# Attenuator.net
KiCad netlist of a schematic drawn in EAGLE
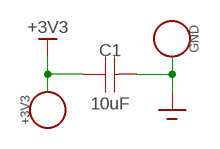
[diagram p0: schematic, sheet 1]
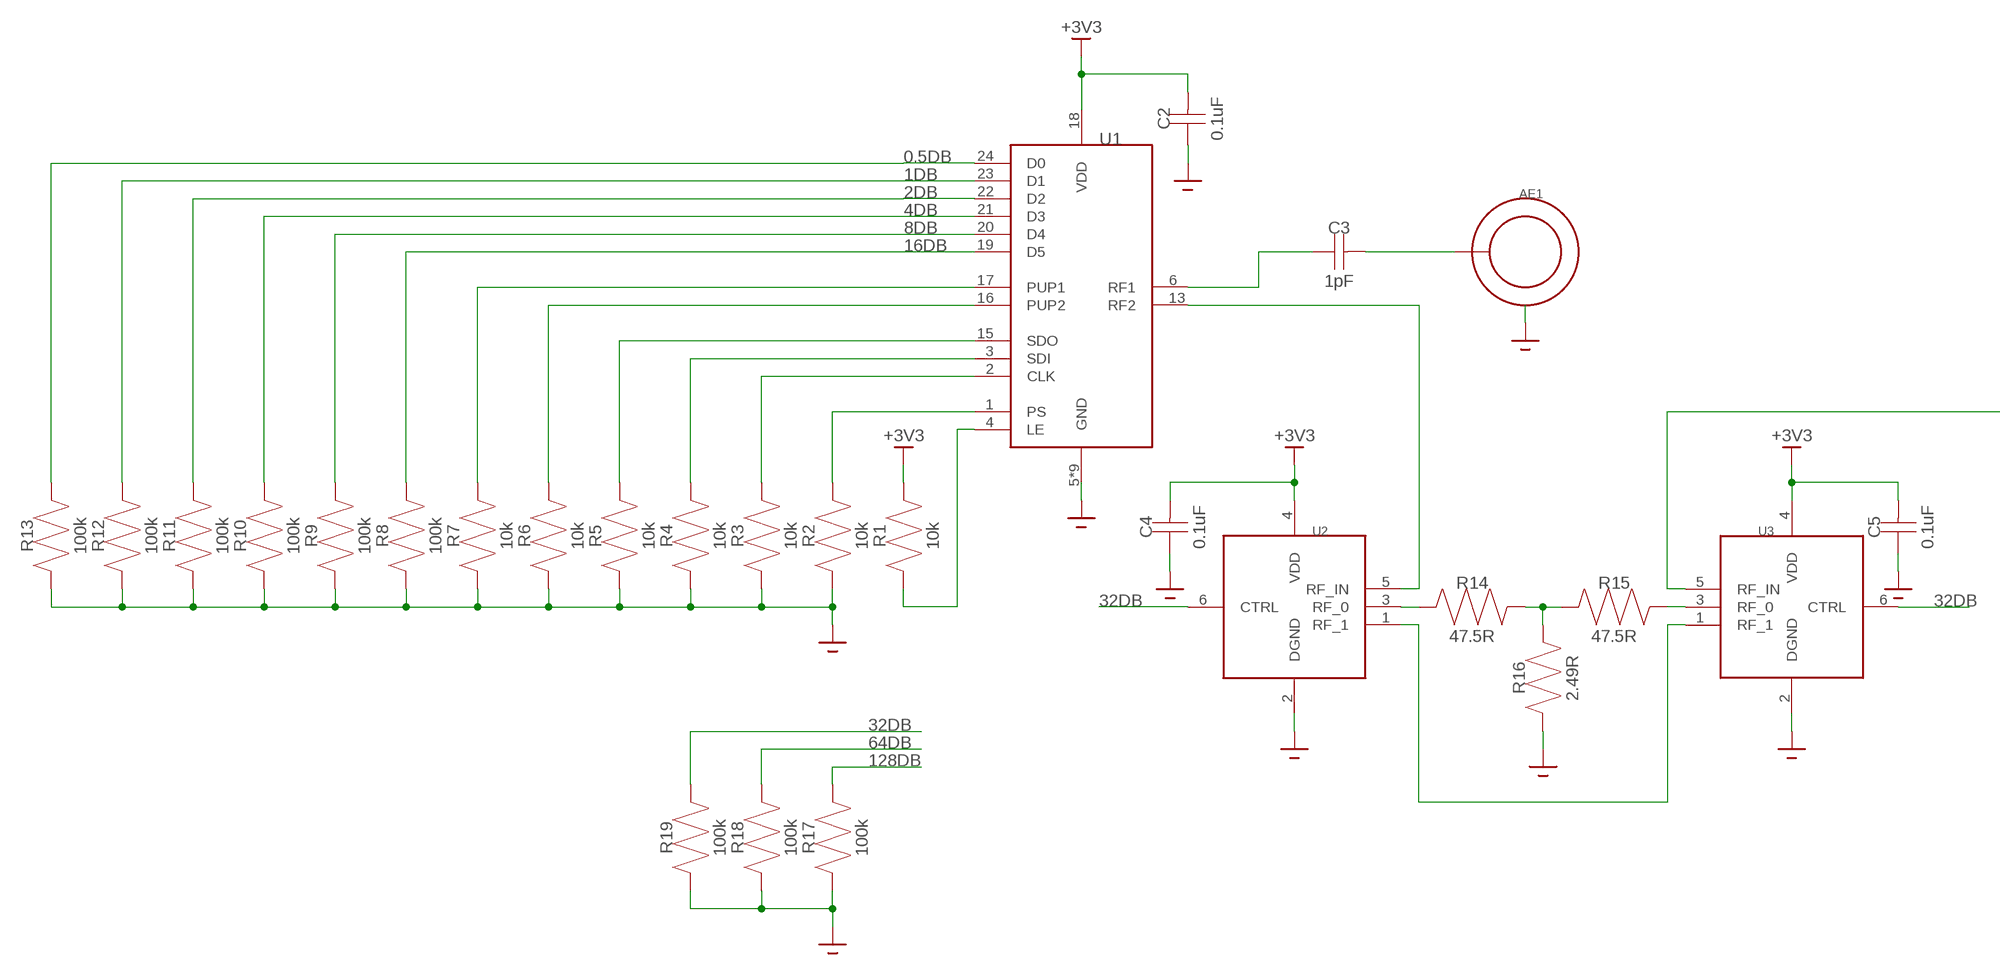
[diagram p1: schematic, sheet 2, part 1 of 2]
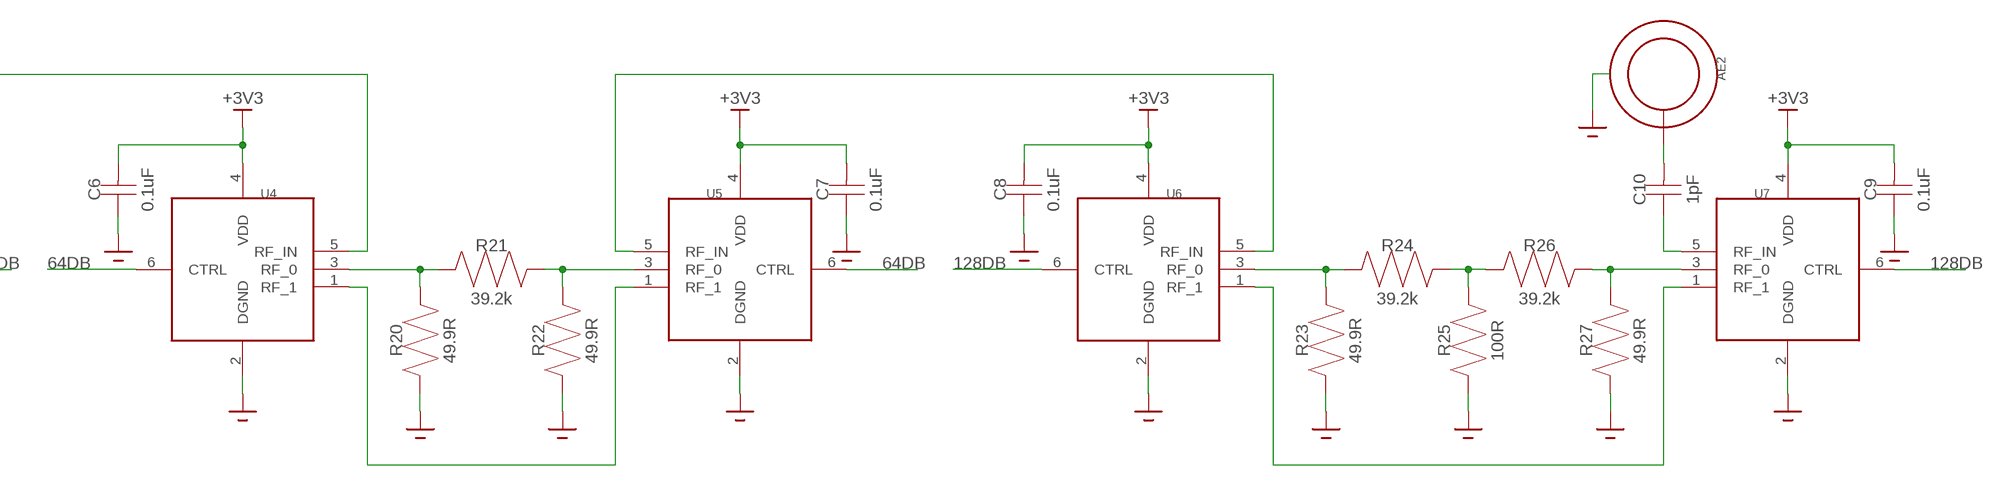
[diagram p2: schematic, sheet 2, part 2 of 2]
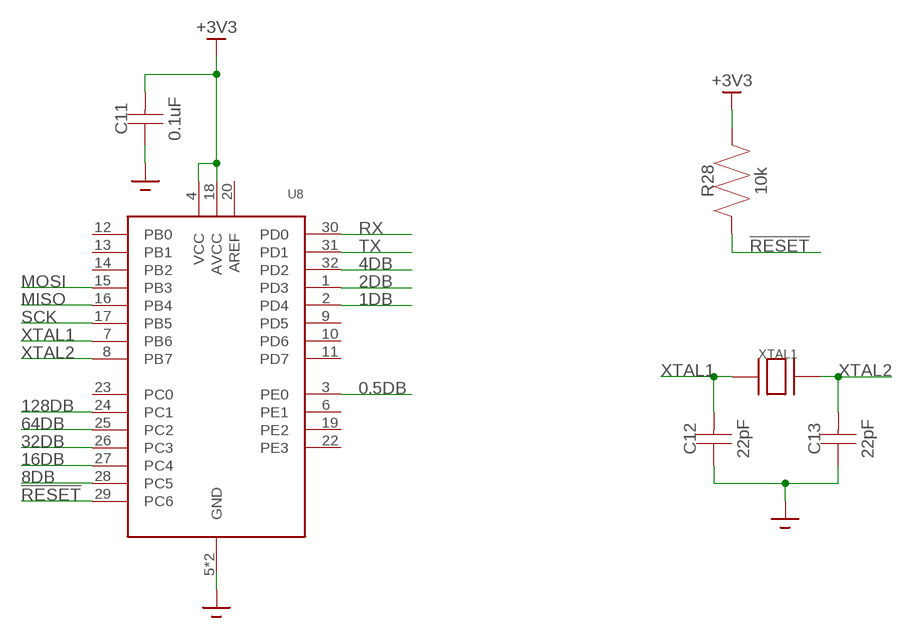
[diagram p3: schematic, sheet 3]
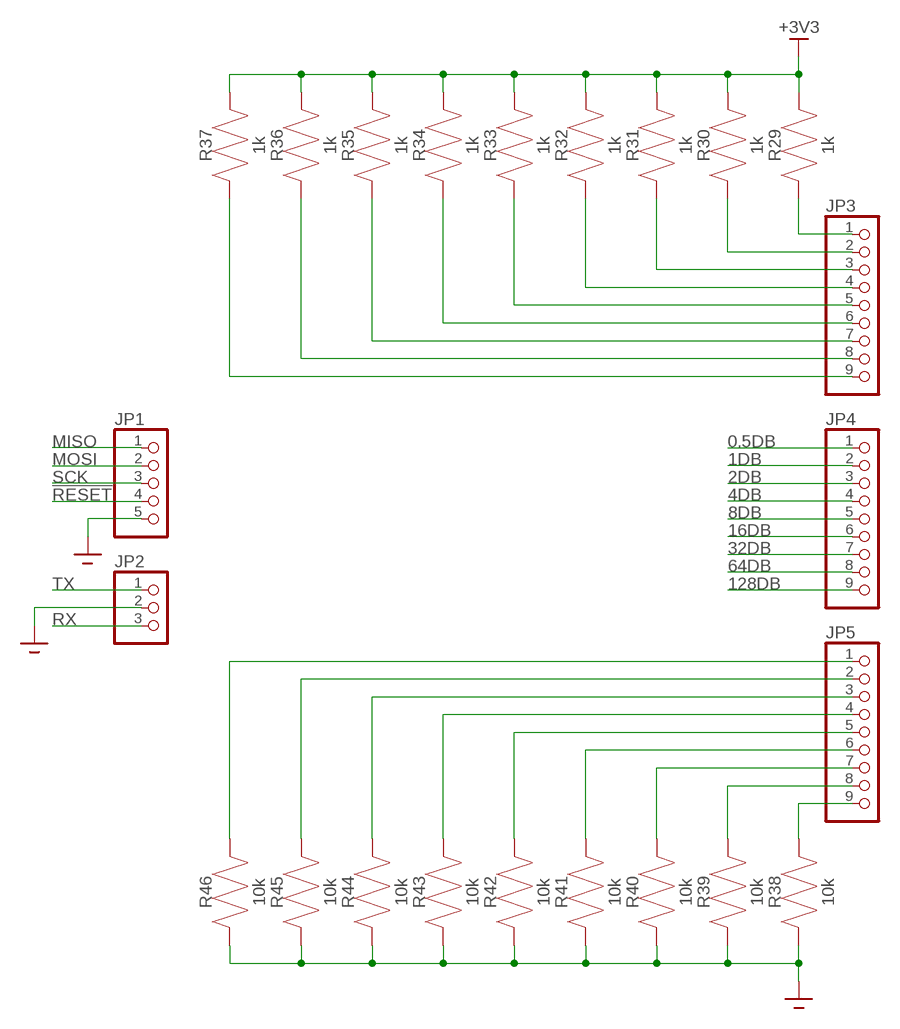
[diagram p4: schematic, sheet 4]

(export (version "E")
  (design (tool "Eeschema 10.0.6"))
  (components
    (comp (ref "C11")
      (value "0.1uF")
      (footprint "eagle-import:0805")
      (libsource (lib "eagle-import") (part "CAPACITOR0805"))
    )
    (comp (ref "C12")
      (value "22pF")
      (footprint "eagle-import:0805")
      (libsource (lib "eagle-import") (part "CAPACITOR0805"))
    )
    (comp (ref "C13")
      (value "22pF")
      (footprint "eagle-import:0805")
      (libsource (lib "eagle-import") (part "CAPACITOR0805"))
    )
    (comp (ref "R28")
      (value "10k")
      (footprint "eagle-import:0805")
      (libsource (lib "eagle-import") (part "RESISTOR0805"))
    )
    (comp (ref "U8")
      (value "ATMEGA328PB32-TQFP")
      (footprint "eagle-import:QFP80P900X900X120-32")
      (libsource (lib "eagle-import") (part "ATMEGA328PB32-TQFP"))
    )
    (comp (ref "XTAL1")
      (value "CRYSTAL")
      (footprint "eagle-import:ABM2")
      (libsource (lib "eagle-import") (part "CRYSTAL"))
    )
    (comp (ref "JP1")
      (value "PINHD-1X5")
      (footprint "eagle-import:1X05")
      (libsource (lib "eagle-import") (part "PINHD-1X5"))
    )
    (comp (ref "JP2")
      (value "PINHD-1X3")
      (footprint "eagle-import:1X03")
      (libsource (lib "eagle-import") (part "PINHD-1X3"))
    )
    (comp (ref "JP3")
      (value "PINHD-1X9")
      (footprint "eagle-import:1X09")
      (libsource (lib "eagle-import") (part "PINHD-1X9"))
    )
    (comp (ref "JP4")
      (value "PINHD-1X9")
      (footprint "eagle-import:1X09")
      (libsource (lib "eagle-import") (part "PINHD-1X9"))
    )
    (comp (ref "JP5")
      (value "PINHD-1X9")
      (footprint "eagle-import:1X09")
      (libsource (lib "eagle-import") (part "PINHD-1X9"))
    )
    (comp (ref "R29")
      (value "1k")
      (footprint "eagle-import:0805")
      (libsource (lib "eagle-import") (part "RESISTOR0805"))
    )
    (comp (ref "R30")
      (value "1k")
      (footprint "eagle-import:0805")
      (libsource (lib "eagle-import") (part "RESISTOR0805"))
    )
    (comp (ref "R31")
      (value "1k")
      (footprint "eagle-import:0805")
      (libsource (lib "eagle-import") (part "RESISTOR0805"))
    )
    (comp (ref "R32")
      (value "1k")
      (footprint "eagle-import:0805")
      (libsource (lib "eagle-import") (part "RESISTOR0805"))
    )
    (comp (ref "R33")
      (value "1k")
      (footprint "eagle-import:0805")
      (libsource (lib "eagle-import") (part "RESISTOR0805"))
    )
    (comp (ref "R34")
      (value "1k")
      (footprint "eagle-import:0805")
      (libsource (lib "eagle-import") (part "RESISTOR0805"))
    )
    (comp (ref "R35")
      (value "1k")
      (footprint "eagle-import:0805")
      (libsource (lib "eagle-import") (part "RESISTOR0805"))
    )
    (comp (ref "R36")
      (value "1k")
      (footprint "eagle-import:0805")
      (libsource (lib "eagle-import") (part "RESISTOR0805"))
    )
    (comp (ref "R37")
      (value "1k")
      (footprint "eagle-import:0805")
      (libsource (lib "eagle-import") (part "RESISTOR0805"))
    )
    (comp (ref "R38")
      (value "10k")
      (footprint "eagle-import:0805")
      (libsource (lib "eagle-import") (part "RESISTOR0805"))
    )
    (comp (ref "R39")
      (value "10k")
      (footprint "eagle-import:0805")
      (libsource (lib "eagle-import") (part "RESISTOR0805"))
    )
    (comp (ref "R40")
      (value "10k")
      (footprint "eagle-import:0805")
      (libsource (lib "eagle-import") (part "RESISTOR0805"))
    )
    (comp (ref "R41")
      (value "10k")
      (footprint "eagle-import:0805")
      (libsource (lib "eagle-import") (part "RESISTOR0805"))
    )
    (comp (ref "R42")
      (value "10k")
      (footprint "eagle-import:0805")
      (libsource (lib "eagle-import") (part "RESISTOR0805"))
    )
    (comp (ref "R43")
      (value "10k")
      (footprint "eagle-import:0805")
      (libsource (lib "eagle-import") (part "RESISTOR0805"))
    )
    (comp (ref "R44")
      (value "10k")
      (footprint "eagle-import:0805")
      (libsource (lib "eagle-import") (part "RESISTOR0805"))
    )
    (comp (ref "R45")
      (value "10k")
      (footprint "eagle-import:0805")
      (libsource (lib "eagle-import") (part "RESISTOR0805"))
    )
    (comp (ref "R46")
      (value "10k")
      (footprint "eagle-import:0805")
      (libsource (lib "eagle-import") (part "RESISTOR0805"))
    )
    (comp (ref "C1")
      (value "10uF")
      (footprint "eagle-import:0805")
      (libsource (lib "eagle-import") (part "CAPACITOR0805"))
    )
    (comp (ref "TP1")
      (value "+3V3")
      (footprint "eagle-import:ALIGATOR-PAD")
      (libsource (lib "eagle-import") (part "ALIGATOR-PAD"))
    )
    (comp (ref "TP2")
      (value "GND")
      (footprint "eagle-import:ALIGATOR-PAD")
      (libsource (lib "eagle-import") (part "ALIGATOR-PAD"))
    )
    (comp (ref "AE1")
      (value "CON-SMA-EDGE-S")
      (footprint "eagle-import:CON-SMA-EDGE-S")
      (libsource (lib "eagle-import") (part "CON-SMA-EDGE-S"))
    )
    (comp (ref "AE2")
      (value "CON-SMA-EDGE-S")
      (footprint "eagle-import:CON-SMA-EDGE-S")
      (libsource (lib "eagle-import") (part "CON-SMA-EDGE-S"))
    )
    (comp (ref "C2")
      (value "0.1uF")
      (footprint "eagle-import:0805")
      (libsource (lib "eagle-import") (part "CAPACITOR0805"))
    )
    (comp (ref "C3")
      (value "1pF")
      (footprint "eagle-import:0805")
      (libsource (lib "eagle-import") (part "CAPACITOR0805"))
    )
    (comp (ref "C4")
      (value "0.1uF")
      (footprint "eagle-import:0805")
      (libsource (lib "eagle-import") (part "CAPACITOR0805"))
    )
    (comp (ref "C5")
      (value "0.1uF")
      (footprint "eagle-import:0805")
      (libsource (lib "eagle-import") (part "CAPACITOR0805"))
    )
    (comp (ref "C6")
      (value "0.1uF")
      (footprint "eagle-import:0805")
      (libsource (lib "eagle-import") (part "CAPACITOR0805"))
    )
    (comp (ref "C7")
      (value "0.1uF")
      (footprint "eagle-import:0805")
      (libsource (lib "eagle-import") (part "CAPACITOR0805"))
    )
    (comp (ref "C8")
      (value "0.1uF")
      (footprint "eagle-import:0805")
      (libsource (lib "eagle-import") (part "CAPACITOR0805"))
    )
    (comp (ref "C9")
      (value "0.1uF")
      (footprint "eagle-import:0805")
      (libsource (lib "eagle-import") (part "CAPACITOR0805"))
    )
    (comp (ref "C10")
      (value "1pF")
      (footprint "eagle-import:0805")
      (libsource (lib "eagle-import") (part "CAPACITOR0805"))
    )
    (comp (ref "R1")
      (value "10k")
      (footprint "eagle-import:0805")
      (libsource (lib "eagle-import") (part "RESISTOR0805"))
    )
    (comp (ref "R2")
      (value "10k")
      (footprint "eagle-import:0805")
      (libsource (lib "eagle-import") (part "RESISTOR0805"))
    )
    (comp (ref "R3")
      (value "10k")
      (footprint "eagle-import:0805")
      (libsource (lib "eagle-import") (part "RESISTOR0805"))
    )
    (comp (ref "R4")
      (value "10k")
      (footprint "eagle-import:0805")
      (libsource (lib "eagle-import") (part "RESISTOR0805"))
    )
    (comp (ref "R5")
      (value "10k")
      (footprint "eagle-import:0805")
      (libsource (lib "eagle-import") (part "RESISTOR0805"))
    )
    (comp (ref "R6")
      (value "10k")
      (footprint "eagle-import:0805")
      (libsource (lib "eagle-import") (part "RESISTOR0805"))
    )
    (comp (ref "R7")
      (value "10k")
      (footprint "eagle-import:0805")
      (libsource (lib "eagle-import") (part "RESISTOR0805"))
    )
    (comp (ref "R8")
      (value "100k")
      (footprint "eagle-import:0805")
      (libsource (lib "eagle-import") (part "RESISTOR0805"))
    )
    (comp (ref "R9")
      (value "100k")
      (footprint "eagle-import:0805")
      (libsource (lib "eagle-import") (part "RESISTOR0805"))
    )
    (comp (ref "R10")
      (value "100k")
      (footprint "eagle-import:0805")
      (libsource (lib "eagle-import") (part "RESISTOR0805"))
    )
    (comp (ref "R11")
      (value "100k")
      (footprint "eagle-import:0805")
      (libsource (lib "eagle-import") (part "RESISTOR0805"))
    )
    (comp (ref "R12")
      (value "100k")
      (footprint "eagle-import:0805")
      (libsource (lib "eagle-import") (part "RESISTOR0805"))
    )
    (comp (ref "R13")
      (value "100k")
      (footprint "eagle-import:0805")
      (libsource (lib "eagle-import") (part "RESISTOR0805"))
    )
    (comp (ref "R14")
      (value "47.5R")
      (footprint "eagle-import:0805")
      (libsource (lib "eagle-import") (part "RESISTOR0805"))
    )
    (comp (ref "R15")
      (value "47.5R")
      (footprint "eagle-import:0805")
      (libsource (lib "eagle-import") (part "RESISTOR0805"))
    )
    (comp (ref "R16")
      (value "2.49R")
      (footprint "eagle-import:0805")
      (libsource (lib "eagle-import") (part "RESISTOR0805"))
    )
    (comp (ref "R17")
      (value "100k")
      (footprint "eagle-import:0805")
      (libsource (lib "eagle-import") (part "RESISTOR0805"))
    )
    (comp (ref "R18")
      (value "100k")
      (footprint "eagle-import:0805")
      (libsource (lib "eagle-import") (part "RESISTOR0805"))
    )
    (comp (ref "R19")
      (value "100k")
      (footprint "eagle-import:0805")
      (libsource (lib "eagle-import") (part "RESISTOR0805"))
    )
    (comp (ref "R20")
      (value "49.9R")
      (footprint "eagle-import:0805")
      (libsource (lib "eagle-import") (part "RESISTOR0805"))
    )
    (comp (ref "R21")
      (value "39.2k")
      (footprint "eagle-import:0805")
      (libsource (lib "eagle-import") (part "RESISTOR0805"))
    )
    (comp (ref "R22")
      (value "49.9R")
      (footprint "eagle-import:0805")
      (libsource (lib "eagle-import") (part "RESISTOR0805"))
    )
    (comp (ref "R23")
      (value "49.9R")
      (footprint "eagle-import:0805")
      (libsource (lib "eagle-import") (part "RESISTOR0805"))
    )
    (comp (ref "R24")
      (value "39.2k")
      (footprint "eagle-import:0805")
      (libsource (lib "eagle-import") (part "RESISTOR0805"))
    )
    (comp (ref "R25")
      (value "100R")
      (footprint "eagle-import:0805")
      (libsource (lib "eagle-import") (part "RESISTOR0805"))
    )
    (comp (ref "R26")
      (value "39.2k")
      (footprint "eagle-import:0805")
      (libsource (lib "eagle-import") (part "RESISTOR0805"))
    )
    (comp (ref "R27")
      (value "49.9R")
      (footprint "eagle-import:0805")
      (libsource (lib "eagle-import") (part "RESISTOR0805"))
    )
    (comp (ref "U1")
      (value "SKY12347-362LF")
      (footprint "eagle-import:QFN50P400X400X100-25T270N")
      (libsource (lib "eagle-import") (part "SKY12347-362LF"))
    )
    (comp (ref "U2")
      (value "BGS12SN6E6327XTSA1")
      (footprint "eagle-import:SON40P70X110X40-6N")
      (libsource (lib "eagle-import") (part "BGS12SN6E6327XTSA1"))
    )
    (comp (ref "U3")
      (value "BGS12SN6E6327XTSA1")
      (footprint "eagle-import:SON40P70X110X40-6N")
      (libsource (lib "eagle-import") (part "BGS12SN6E6327XTSA1"))
    )
    (comp (ref "U4")
      (value "BGS12SN6E6327XTSA1")
      (footprint "eagle-import:SON40P70X110X40-6N")
      (libsource (lib "eagle-import") (part "BGS12SN6E6327XTSA1"))
    )
    (comp (ref "U5")
      (value "BGS12SN6E6327XTSA1")
      (footprint "eagle-import:SON40P70X110X40-6N")
      (libsource (lib "eagle-import") (part "BGS12SN6E6327XTSA1"))
    )
    (comp (ref "U6")
      (value "BGS12SN6E6327XTSA1")
      (footprint "eagle-import:SON40P70X110X40-6N")
      (libsource (lib "eagle-import") (part "BGS12SN6E6327XTSA1"))
    )
    (comp (ref "U7")
      (value "BGS12SN6E6327XTSA1")
      (footprint "eagle-import:SON40P70X110X40-6N")
      (libsource (lib "eagle-import") (part "BGS12SN6E6327XTSA1"))
    )
  )
  (nets
    (net (code "1") (name "+3V3") (class "Default")
      (node (ref "C1") (pin "P$1") (pinfunction "P$1_P$1") (pintype "passive"))
      (node (ref "C11") (pin "P$2") (pinfunction "P$2_P$2") (pintype "passive"))
      (node (ref "C2") (pin "P$2") (pinfunction "P$2_P$2") (pintype "passive"))
      (node (ref "C4") (pin "P$2") (pinfunction "P$2_P$2") (pintype "passive"))
      (node (ref "C5") (pin "P$2") (pinfunction "P$2_P$2") (pintype "passive"))
      (node (ref "C6") (pin "P$2") (pinfunction "P$2_P$2") (pintype "passive"))
      (node (ref "C7") (pin "P$2") (pinfunction "P$2_P$2") (pintype "passive"))
      (node (ref "C8") (pin "P$2") (pinfunction "P$2_P$2") (pintype "passive"))
      (node (ref "C9") (pin "P$2") (pinfunction "P$2_P$2") (pintype "passive"))
      (node (ref "R1") (pin "P$2") (pinfunction "P$2_P$2") (pintype "passive"))
      (node (ref "R28") (pin "P$2") (pinfunction "P$2_P$2") (pintype "passive"))
      (node (ref "R29") (pin "P$2") (pinfunction "P$2_P$2") (pintype "passive"))
      (node (ref "R30") (pin "P$2") (pinfunction "P$2_P$2") (pintype "passive"))
      (node (ref "R31") (pin "P$2") (pinfunction "P$2_P$2") (pintype "passive"))
      (node (ref "R32") (pin "P$2") (pinfunction "P$2_P$2") (pintype "passive"))
      (node (ref "R33") (pin "P$2") (pinfunction "P$2_P$2") (pintype "passive"))
      (node (ref "R34") (pin "P$2") (pinfunction "P$2_P$2") (pintype "passive"))
      (node (ref "R35") (pin "P$2") (pinfunction "P$2_P$2") (pintype "passive"))
      (node (ref "R36") (pin "P$2") (pinfunction "P$2_P$2") (pintype "passive"))
      (node (ref "R37") (pin "P$2") (pinfunction "P$2_P$2") (pintype "passive"))
      (node (ref "TP1") (pin "P$1") (pinfunction "P$1_P$1") (pintype "bidirectional"))
      (node (ref "TP1") (pin "P$2") (pinfunction "P$1_P$2") (pintype "bidirectional"))
      (node (ref "TP1") (pin "P$3") (pinfunction "P$1_P$3") (pintype "bidirectional"))
      (node (ref "TP1") (pin "P$4") (pinfunction "P$1_P$4") (pintype "bidirectional"))
      (node (ref "TP1") (pin "P$5") (pinfunction "P$1_P$5") (pintype "bidirectional"))
      (node (ref "TP1") (pin "P$6") (pinfunction "P$1_P$6") (pintype "bidirectional"))
      (node (ref "U1") (pin "18") (pinfunction "VDD_18") (pintype "power_in"))
      (node (ref "U2") (pin "4") (pinfunction "VDD_4") (pintype "bidirectional"))
      (node (ref "U3") (pin "4") (pinfunction "VDD_4") (pintype "bidirectional"))
      (node (ref "U4") (pin "4") (pinfunction "VDD_4") (pintype "bidirectional"))
      (node (ref "U5") (pin "4") (pinfunction "VDD_4") (pintype "bidirectional"))
      (node (ref "U6") (pin "4") (pinfunction "VDD_4") (pintype "bidirectional"))
      (node (ref "U7") (pin "4") (pinfunction "VDD_4") (pintype "bidirectional"))
      (node (ref "U8") (pin "18") (pinfunction "AVCC_18") (pintype "power_in"))
      (node (ref "U8") (pin "4") (pinfunction "VCC_4") (pintype "power_in"))
    )
    (net (code "2") (name "0.5DB") (class "Default")
      (node (ref "JP4") (pin "1") (pinfunction "1_1") (pintype "passive"))
      (node (ref "R13") (pin "P$2") (pinfunction "P$2_P$2") (pintype "passive"))
      (node (ref "U1") (pin "24") (pinfunction "D0_24") (pintype "input"))
      (node (ref "U8") (pin "3") (pinfunction "PE0_3") (pintype "bidirectional"))
    )
    (net (code "3") (name "1DB") (class "Default")
      (node (ref "JP4") (pin "2") (pinfunction "2_2") (pintype "passive"))
      (node (ref "R12") (pin "P$2") (pinfunction "P$2_P$2") (pintype "passive"))
      (node (ref "U1") (pin "23") (pinfunction "D1_23") (pintype "input"))
      (node (ref "U8") (pin "2") (pinfunction "PD4_2") (pintype "bidirectional"))
    )
    (net (code "4") (name "2DB") (class "Default")
      (node (ref "JP4") (pin "3") (pinfunction "3_3") (pintype "passive"))
      (node (ref "R11") (pin "P$2") (pinfunction "P$2_P$2") (pintype "passive"))
      (node (ref "U1") (pin "22") (pinfunction "D2_22") (pintype "input"))
      (node (ref "U8") (pin "1") (pinfunction "PD3_1") (pintype "bidirectional"))
    )
    (net (code "5") (name "4DB") (class "Default")
      (node (ref "JP4") (pin "4") (pinfunction "4_4") (pintype "passive"))
      (node (ref "R10") (pin "P$2") (pinfunction "P$2_P$2") (pintype "passive"))
      (node (ref "U1") (pin "21") (pinfunction "D3_21") (pintype "input"))
      (node (ref "U8") (pin "32") (pinfunction "PD2_32") (pintype "bidirectional"))
    )
    (net (code "6") (name "8DB") (class "Default")
      (node (ref "JP4") (pin "5") (pinfunction "5_5") (pintype "passive"))
      (node (ref "R9") (pin "P$2") (pinfunction "P$2_P$2") (pintype "passive"))
      (node (ref "U1") (pin "20") (pinfunction "D4_20") (pintype "input"))
      (node (ref "U8") (pin "28") (pinfunction "PC5_28") (pintype "bidirectional"))
    )
    (net (code "7") (name "16DB") (class "Default")
      (node (ref "JP4") (pin "6") (pinfunction "6_6") (pintype "passive"))
      (node (ref "R8") (pin "P$2") (pinfunction "P$2_P$2") (pintype "passive"))
      (node (ref "U1") (pin "19") (pinfunction "D5_19") (pintype "input"))
      (node (ref "U8") (pin "27") (pinfunction "PC4_27") (pintype "bidirectional"))
    )
    (net (code "8") (name "32DB") (class "Default")
      (node (ref "JP4") (pin "7") (pinfunction "7_7") (pintype "passive"))
      (node (ref "R19") (pin "P$2") (pinfunction "P$2_P$2") (pintype "passive"))
      (node (ref "U2") (pin "6") (pinfunction "CTRL_6") (pintype "bidirectional"))
      (node (ref "U3") (pin "6") (pinfunction "CTRL_6") (pintype "bidirectional"))
      (node (ref "U8") (pin "26") (pinfunction "PC3_26") (pintype "bidirectional"))
    )
    (net (code "9") (name "64DB") (class "Default")
      (node (ref "JP4") (pin "8") (pinfunction "8_8") (pintype "passive"))
      (node (ref "R18") (pin "P$2") (pinfunction "P$2_P$2") (pintype "passive"))
      (node (ref "U4") (pin "6") (pinfunction "CTRL_6") (pintype "bidirectional"))
      (node (ref "U5") (pin "6") (pinfunction "CTRL_6") (pintype "bidirectional"))
      (node (ref "U8") (pin "25") (pinfunction "PC2_25") (pintype "bidirectional"))
    )
    (net (code "10") (name "128DB") (class "Default")
      (node (ref "JP4") (pin "9") (pinfunction "9_9") (pintype "passive"))
      (node (ref "R17") (pin "P$2") (pinfunction "P$2_P$2") (pintype "passive"))
      (node (ref "U6") (pin "6") (pinfunction "CTRL_6") (pintype "bidirectional"))
      (node (ref "U7") (pin "6") (pinfunction "CTRL_6") (pintype "bidirectional"))
      (node (ref "U8") (pin "24") (pinfunction "PC1_24") (pintype "bidirectional"))
    )
    (net (code "11") (name "AREF") (class "Default")
      (node (ref "U8") (pin "20") (pinfunction "AREF_20") (pintype "power_in"))
    )
    (net (code "12") (name "GND") (class "Default")
      (node (ref "AE1") (pin "GND1") (pinfunction "GND_GND1") (pintype "passive"))
      (node (ref "AE1") (pin "GND2") (pinfunction "GND_GND2") (pintype "passive"))
      (node (ref "AE1") (pin "GND3") (pinfunction "GND_GND3") (pintype "passive"))
      (node (ref "AE1") (pin "GND4") (pinfunction "GND_GND4") (pintype "passive"))
      (node (ref "AE2") (pin "GND1") (pinfunction "GND_GND1") (pintype "passive"))
      (node (ref "AE2") (pin "GND2") (pinfunction "GND_GND2") (pintype "passive"))
      (node (ref "AE2") (pin "GND3") (pinfunction "GND_GND3") (pintype "passive"))
      (node (ref "AE2") (pin "GND4") (pinfunction "GND_GND4") (pintype "passive"))
      (node (ref "C1") (pin "P$2") (pinfunction "P$2_P$2") (pintype "passive"))
      (node (ref "C11") (pin "P$1") (pinfunction "P$1_P$1") (pintype "passive"))
      (node (ref "C12") (pin "P$1") (pinfunction "P$1_P$1") (pintype "passive"))
      (node (ref "C13") (pin "P$1") (pinfunction "P$1_P$1") (pintype "passive"))
      (node (ref "C2") (pin "P$1") (pinfunction "P$1_P$1") (pintype "passive"))
      (node (ref "C4") (pin "P$1") (pinfunction "P$1_P$1") (pintype "passive"))
      (node (ref "C5") (pin "P$1") (pinfunction "P$1_P$1") (pintype "passive"))
      (node (ref "C6") (pin "P$1") (pinfunction "P$1_P$1") (pintype "passive"))
      (node (ref "C7") (pin "P$1") (pinfunction "P$1_P$1") (pintype "passive"))
      (node (ref "C8") (pin "P$1") (pinfunction "P$1_P$1") (pintype "passive"))
      (node (ref "C9") (pin "P$1") (pinfunction "P$1_P$1") (pintype "passive"))
      (node (ref "JP1") (pin "5") (pinfunction "5_5") (pintype "passive"))
      (node (ref "JP2") (pin "2") (pinfunction "2_2") (pintype "passive"))
      (node (ref "R10") (pin "P$1") (pinfunction "P$1_P$1") (pintype "passive"))
      (node (ref "R11") (pin "P$1") (pinfunction "P$1_P$1") (pintype "passive"))
      (node (ref "R12") (pin "P$1") (pinfunction "P$1_P$1") (pintype "passive"))
      (node (ref "R13") (pin "P$1") (pinfunction "P$1_P$1") (pintype "passive"))
      (node (ref "R16") (pin "P$1") (pinfunction "P$1_P$1") (pintype "passive"))
      (node (ref "R17") (pin "P$1") (pinfunction "P$1_P$1") (pintype "passive"))
      (node (ref "R18") (pin "P$1") (pinfunction "P$1_P$1") (pintype "passive"))
      (node (ref "R19") (pin "P$1") (pinfunction "P$1_P$1") (pintype "passive"))
      (node (ref "R2") (pin "P$1") (pinfunction "P$1_P$1") (pintype "passive"))
      (node (ref "R20") (pin "P$1") (pinfunction "P$1_P$1") (pintype "passive"))
      (node (ref "R22") (pin "P$1") (pinfunction "P$1_P$1") (pintype "passive"))
      (node (ref "R23") (pin "P$1") (pinfunction "P$1_P$1") (pintype "passive"))
      (node (ref "R25") (pin "P$1") (pinfunction "P$1_P$1") (pintype "passive"))
      (node (ref "R27") (pin "P$1") (pinfunction "P$1_P$1") (pintype "passive"))
      (node (ref "R3") (pin "P$1") (pinfunction "P$1_P$1") (pintype "passive"))
      (node (ref "R38") (pin "P$1") (pinfunction "P$1_P$1") (pintype "passive"))
      (node (ref "R39") (pin "P$1") (pinfunction "P$1_P$1") (pintype "passive"))
      (node (ref "R4") (pin "P$1") (pinfunction "P$1_P$1") (pintype "passive"))
      (node (ref "R40") (pin "P$1") (pinfunction "P$1_P$1") (pintype "passive"))
      (node (ref "R41") (pin "P$1") (pinfunction "P$1_P$1") (pintype "passive"))
      (node (ref "R42") (pin "P$1") (pinfunction "P$1_P$1") (pintype "passive"))
      (node (ref "R43") (pin "P$1") (pinfunction "P$1_P$1") (pintype "passive"))
      (node (ref "R44") (pin "P$1") (pinfunction "P$1_P$1") (pintype "passive"))
      (node (ref "R45") (pin "P$1") (pinfunction "P$1_P$1") (pintype "passive"))
      (node (ref "R46") (pin "P$1") (pinfunction "P$1_P$1") (pintype "passive"))
      (node (ref "R5") (pin "P$1") (pinfunction "P$1_P$1") (pintype "passive"))
      (node (ref "R6") (pin "P$1") (pinfunction "P$1_P$1") (pintype "passive"))
      (node (ref "R7") (pin "P$1") (pinfunction "P$1_P$1") (pintype "passive"))
      (node (ref "R8") (pin "P$1") (pinfunction "P$1_P$1") (pintype "passive"))
      (node (ref "R9") (pin "P$1") (pinfunction "P$1_P$1") (pintype "passive"))
      (node (ref "TP2") (pin "P$1") (pinfunction "P$1_P$1") (pintype "bidirectional"))
      (node (ref "TP2") (pin "P$2") (pinfunction "P$1_P$2") (pintype "bidirectional"))
      (node (ref "TP2") (pin "P$3") (pinfunction "P$1_P$3") (pintype "bidirectional"))
      (node (ref "TP2") (pin "P$4") (pinfunction "P$1_P$4") (pintype "bidirectional"))
      (node (ref "TP2") (pin "P$5") (pinfunction "P$1_P$5") (pintype "bidirectional"))
      (node (ref "TP2") (pin "P$6") (pinfunction "P$1_P$6") (pintype "bidirectional"))
      (node (ref "U1") (pin "10") (pinfunction "GND_10") (pintype "passive"))
      (node (ref "U1") (pin "11") (pinfunction "GND_11") (pintype "passive"))
      (node (ref "U1") (pin "12") (pinfunction "GND_12") (pintype "passive"))
      (node (ref "U1") (pin "14") (pinfunction "GND_14") (pintype "passive"))
      (node (ref "U1") (pin "25") (pinfunction "GND_25") (pintype "passive"))
      (node (ref "U1") (pin "5") (pinfunction "GND_5") (pintype "passive"))
      (node (ref "U1") (pin "7") (pinfunction "GND_7") (pintype "passive"))
      (node (ref "U1") (pin "8") (pinfunction "GND_8") (pintype "passive"))
      (node (ref "U1") (pin "9") (pinfunction "GND_9") (pintype "passive"))
      (node (ref "U2") (pin "2") (pinfunction "DGND_2") (pintype "bidirectional"))
      (node (ref "U3") (pin "2") (pinfunction "DGND_2") (pintype "bidirectional"))
      (node (ref "U4") (pin "2") (pinfunction "DGND_2") (pintype "bidirectional"))
      (node (ref "U5") (pin "2") (pinfunction "DGND_2") (pintype "bidirectional"))
      (node (ref "U6") (pin "2") (pinfunction "DGND_2") (pintype "bidirectional"))
      (node (ref "U7") (pin "2") (pinfunction "DGND_2") (pintype "bidirectional"))
      (node (ref "U8") (pin "21") (pinfunction "GND_21") (pintype "passive"))
      (node (ref "U8") (pin "5") (pinfunction "GND_5") (pintype "passive"))
    )
    (net (code "13") (name "MISO") (class "Default")
      (node (ref "JP1") (pin "1") (pinfunction "1_1") (pintype "passive"))
      (node (ref "U8") (pin "16") (pinfunction "PB4_16") (pintype "bidirectional"))
    )
    (net (code "14") (name "MOSI") (class "Default")
      (node (ref "JP1") (pin "2") (pinfunction "2_2") (pintype "passive"))
      (node (ref "U8") (pin "15") (pinfunction "PB3_15") (pintype "bidirectional"))
    )
    (net (code "15") (name "Net-(AE1-OUT)") (class "Default")
      (node (ref "AE1") (pin "CENTER") (pinfunction "OUT_CENTER") (pintype "output"))
      (node (ref "C3") (pin "P$2") (pinfunction "P$2_P$2") (pintype "passive"))
    )
    (net (code "16") (name "Net-(AE2-OUT)") (class "Default")
      (node (ref "AE2") (pin "CENTER") (pinfunction "OUT_CENTER") (pintype "output"))
      (node (ref "C10") (pin "P$2") (pinfunction "P$2_P$2") (pintype "passive"))
    )
    (net (code "17") (name "Net-(JP3-Pad1)") (class "Default")
      (node (ref "JP3") (pin "1") (pinfunction "1_1") (pintype "passive"))
      (node (ref "R29") (pin "P$1") (pinfunction "P$1_P$1") (pintype "passive"))
    )
    (net (code "18") (name "Net-(JP3-Pad2)") (class "Default")
      (node (ref "JP3") (pin "2") (pinfunction "2_2") (pintype "passive"))
      (node (ref "R30") (pin "P$1") (pinfunction "P$1_P$1") (pintype "passive"))
    )
    (net (code "19") (name "Net-(JP3-Pad3)") (class "Default")
      (node (ref "JP3") (pin "3") (pinfunction "3_3") (pintype "passive"))
      (node (ref "R31") (pin "P$1") (pinfunction "P$1_P$1") (pintype "passive"))
    )
    (net (code "20") (name "Net-(JP3-Pad4)") (class "Default")
      (node (ref "JP3") (pin "4") (pinfunction "4_4") (pintype "passive"))
      (node (ref "R32") (pin "P$1") (pinfunction "P$1_P$1") (pintype "passive"))
    )
    (net (code "21") (name "Net-(JP3-Pad5)") (class "Default")
      (node (ref "JP3") (pin "5") (pinfunction "5_5") (pintype "passive"))
      (node (ref "R33") (pin "P$1") (pinfunction "P$1_P$1") (pintype "passive"))
    )
    (net (code "22") (name "Net-(JP3-Pad6)") (class "Default")
      (node (ref "JP3") (pin "6") (pinfunction "6_6") (pintype "passive"))
      (node (ref "R34") (pin "P$1") (pinfunction "P$1_P$1") (pintype "passive"))
    )
    (net (code "23") (name "Net-(JP3-Pad7)") (class "Default")
      (node (ref "JP3") (pin "7") (pinfunction "7_7") (pintype "passive"))
      (node (ref "R35") (pin "P$1") (pinfunction "P$1_P$1") (pintype "passive"))
    )
    (net (code "24") (name "Net-(JP3-Pad8)") (class "Default")
      (node (ref "JP3") (pin "8") (pinfunction "8_8") (pintype "passive"))
      (node (ref "R36") (pin "P$1") (pinfunction "P$1_P$1") (pintype "passive"))
    )
    (net (code "25") (name "Net-(JP3-Pad9)") (class "Default")
      (node (ref "JP3") (pin "9") (pinfunction "9_9") (pintype "passive"))
      (node (ref "R37") (pin "P$1") (pinfunction "P$1_P$1") (pintype "passive"))
    )
    (net (code "26") (name "Net-(JP5-Pad1)") (class "Default")
      (node (ref "JP5") (pin "1") (pinfunction "1_1") (pintype "passive"))
      (node (ref "R46") (pin "P$2") (pinfunction "P$2_P$2") (pintype "passive"))
    )
    (net (code "27") (name "Net-(JP5-Pad2)") (class "Default")
      (node (ref "JP5") (pin "2") (pinfunction "2_2") (pintype "passive"))
      (node (ref "R45") (pin "P$2") (pinfunction "P$2_P$2") (pintype "passive"))
    )
    (net (code "28") (name "Net-(JP5-Pad3)") (class "Default")
      (node (ref "JP5") (pin "3") (pinfunction "3_3") (pintype "passive"))
      (node (ref "R44") (pin "P$2") (pinfunction "P$2_P$2") (pintype "passive"))
    )
    (net (code "29") (name "Net-(JP5-Pad4)") (class "Default")
      (node (ref "JP5") (pin "4") (pinfunction "4_4") (pintype "passive"))
      (node (ref "R43") (pin "P$2") (pinfunction "P$2_P$2") (pintype "passive"))
    )
    (net (code "30") (name "Net-(JP5-Pad5)") (class "Default")
      (node (ref "JP5") (pin "5") (pinfunction "5_5") (pintype "passive"))
      (node (ref "R42") (pin "P$2") (pinfunction "P$2_P$2") (pintype "passive"))
    )
    (net (code "31") (name "Net-(JP5-Pad6)") (class "Default")
      (node (ref "JP5") (pin "6") (pinfunction "6_6") (pintype "passive"))
      (node (ref "R41") (pin "P$2") (pinfunction "P$2_P$2") (pintype "passive"))
    )
    (net (code "32") (name "Net-(JP5-Pad7)") (class "Default")
      (node (ref "JP5") (pin "7") (pinfunction "7_7") (pintype "passive"))
      (node (ref "R40") (pin "P$2") (pinfunction "P$2_P$2") (pintype "passive"))
    )
    (net (code "33") (name "Net-(JP5-Pad8)") (class "Default")
      (node (ref "JP5") (pin "8") (pinfunction "8_8") (pintype "passive"))
      (node (ref "R39") (pin "P$2") (pinfunction "P$2_P$2") (pintype "passive"))
    )
    (net (code "34") (name "Net-(JP5-Pad9)") (class "Default")
      (node (ref "JP5") (pin "9") (pinfunction "9_9") (pintype "passive"))
      (node (ref "R38") (pin "P$2") (pinfunction "P$2_P$2") (pintype "passive"))
    )
    (net (code "35") (name "Net-(R14-PadP$2)") (class "Default")
      (node (ref "R14") (pin "P$2") (pinfunction "P$2_P$2") (pintype "passive"))
      (node (ref "R15") (pin "P$1") (pinfunction "P$1_P$1") (pintype "passive"))
      (node (ref "R16") (pin "P$2") (pinfunction "P$2_P$2") (pintype "passive"))
    )
    (net (code "36") (name "Net-(R24-PadP$2)") (class "Default")
      (node (ref "R24") (pin "P$2") (pinfunction "P$2_P$2") (pintype "passive"))
      (node (ref "R25") (pin "P$2") (pinfunction "P$2_P$2") (pintype "passive"))
      (node (ref "R26") (pin "P$1") (pinfunction "P$1_P$1") (pintype "passive"))
    )
    (net (code "37") (name "Net-(U1-CLK)") (class "Default")
      (node (ref "R3") (pin "P$2") (pinfunction "P$2_P$2") (pintype "passive"))
      (node (ref "U1") (pin "2") (pinfunction "CLK_2") (pintype "input"))
    )
    (net (code "38") (name "Net-(U1-LE)") (class "Default")
      (node (ref "R1") (pin "P$1") (pinfunction "P$1_P$1") (pintype "passive"))
      (node (ref "U1") (pin "4") (pinfunction "LE_4") (pintype "input"))
    )
    (net (code "39") (name "Net-(U1-PS)") (class "Default")
      (node (ref "R2") (pin "P$2") (pinfunction "P$2_P$2") (pintype "passive"))
      (node (ref "U1") (pin "1") (pinfunction "PS_1") (pintype "input"))
    )
    (net (code "40") (name "Net-(U1-PUP1)") (class "Default")
      (node (ref "R7") (pin "P$2") (pinfunction "P$2_P$2") (pintype "passive"))
      (node (ref "U1") (pin "17") (pinfunction "PUP1_17") (pintype "input"))
    )
    (net (code "41") (name "Net-(U1-PUP2)") (class "Default")
      (node (ref "R6") (pin "P$2") (pinfunction "P$2_P$2") (pintype "passive"))
      (node (ref "U1") (pin "16") (pinfunction "PUP2_16") (pintype "input"))
    )
    (net (code "42") (name "Net-(U1-RF1)") (class "Default")
      (node (ref "C3") (pin "P$1") (pinfunction "P$1_P$1") (pintype "passive"))
      (node (ref "U1") (pin "6") (pinfunction "RF1_6") (pintype "bidirectional"))
    )
    (net (code "43") (name "Net-(U1-RF2)") (class "Default")
      (node (ref "U1") (pin "13") (pinfunction "RF2_13") (pintype "bidirectional"))
      (node (ref "U2") (pin "5") (pinfunction "RF_IN_5") (pintype "bidirectional"))
    )
    (net (code "44") (name "Net-(U1-SDI)") (class "Default")
      (node (ref "R4") (pin "P$2") (pinfunction "P$2_P$2") (pintype "passive"))
      (node (ref "U1") (pin "3") (pinfunction "SDI_3") (pintype "input"))
    )
    (net (code "45") (name "Net-(U1-SDO)") (class "Default")
      (node (ref "R5") (pin "P$2") (pinfunction "P$2_P$2") (pintype "passive"))
      (node (ref "U1") (pin "15") (pinfunction "SDO_15") (pintype "output"))
    )
    (net (code "46") (name "Net-(U2-RF_0)") (class "Default")
      (node (ref "R14") (pin "P$1") (pinfunction "P$1_P$1") (pintype "passive"))
      (node (ref "U2") (pin "3") (pinfunction "RF_0_3") (pintype "bidirectional"))
    )
    (net (code "47") (name "Net-(U2-RF_1)") (class "Default")
      (node (ref "U2") (pin "1") (pinfunction "RF_1_1") (pintype "bidirectional"))
      (node (ref "U3") (pin "1") (pinfunction "RF_1_1") (pintype "bidirectional"))
    )
    (net (code "48") (name "Net-(U3-RF_0)") (class "Default")
      (node (ref "R15") (pin "P$2") (pinfunction "P$2_P$2") (pintype "passive"))
      (node (ref "U3") (pin "3") (pinfunction "RF_0_3") (pintype "bidirectional"))
    )
    (net (code "49") (name "Net-(U3-RF_IN)") (class "Default")
      (node (ref "U3") (pin "5") (pinfunction "RF_IN_5") (pintype "bidirectional"))
      (node (ref "U4") (pin "5") (pinfunction "RF_IN_5") (pintype "bidirectional"))
    )
    (net (code "50") (name "Net-(U4-RF_0)") (class "Default")
      (node (ref "R20") (pin "P$2") (pinfunction "P$2_P$2") (pintype "passive"))
      (node (ref "R21") (pin "P$1") (pinfunction "P$1_P$1") (pintype "passive"))
      (node (ref "U4") (pin "3") (pinfunction "RF_0_3") (pintype "bidirectional"))
    )
    (net (code "51") (name "Net-(U4-RF_1)") (class "Default")
      (node (ref "U4") (pin "1") (pinfunction "RF_1_1") (pintype "bidirectional"))
      (node (ref "U5") (pin "1") (pinfunction "RF_1_1") (pintype "bidirectional"))
    )
    (net (code "52") (name "Net-(U5-RF_0)") (class "Default")
      (node (ref "R21") (pin "P$2") (pinfunction "P$2_P$2") (pintype "passive"))
      (node (ref "R22") (pin "P$2") (pinfunction "P$2_P$2") (pintype "passive"))
      (node (ref "U5") (pin "3") (pinfunction "RF_0_3") (pintype "bidirectional"))
    )
    (net (code "53") (name "Net-(U5-RF_IN)") (class "Default")
      (node (ref "U5") (pin "5") (pinfunction "RF_IN_5") (pintype "bidirectional"))
      (node (ref "U6") (pin "5") (pinfunction "RF_IN_5") (pintype "bidirectional"))
    )
    (net (code "54") (name "Net-(U6-RF_0)") (class "Default")
      (node (ref "R23") (pin "P$2") (pinfunction "P$2_P$2") (pintype "passive"))
      (node (ref "R24") (pin "P$1") (pinfunction "P$1_P$1") (pintype "passive"))
      (node (ref "U6") (pin "3") (pinfunction "RF_0_3") (pintype "bidirectional"))
    )
    (net (code "55") (name "Net-(U6-RF_1)") (class "Default")
      (node (ref "U6") (pin "1") (pinfunction "RF_1_1") (pintype "bidirectional"))
      (node (ref "U7") (pin "1") (pinfunction "RF_1_1") (pintype "bidirectional"))
    )
    (net (code "56") (name "Net-(U7-RF_0)") (class "Default")
      (node (ref "R26") (pin "P$2") (pinfunction "P$2_P$2") (pintype "passive"))
      (node (ref "R27") (pin "P$2") (pinfunction "P$2_P$2") (pintype "passive"))
      (node (ref "U7") (pin "3") (pinfunction "RF_0_3") (pintype "bidirectional"))
    )
    (net (code "57") (name "Net-(U7-RF_IN)") (class "Default")
      (node (ref "C10") (pin "P$1") (pinfunction "P$1_P$1") (pintype "passive"))
      (node (ref "U7") (pin "5") (pinfunction "RF_IN_5") (pintype "bidirectional"))
    )
    (net (code "58") (name "RX") (class "Default")
      (node (ref "JP2") (pin "3") (pinfunction "3_3") (pintype "passive"))
      (node (ref "U8") (pin "30") (pinfunction "PD0_30") (pintype "bidirectional"))
    )
    (net (code "59") (name "SCK") (class "Default")
      (node (ref "JP1") (pin "3") (pinfunction "3_3") (pintype "passive"))
      (node (ref "U8") (pin "17") (pinfunction "PB5_17") (pintype "bidirectional"))
    )
    (net (code "60") (name "TX") (class "Default")
      (node (ref "JP2") (pin "1") (pinfunction "1_1") (pintype "passive"))
      (node (ref "U8") (pin "31") (pinfunction "PD1_31") (pintype "bidirectional"))
    )
    (net (code "61") (name "XTAL1") (class "Default")
      (node (ref "C12") (pin "P$2") (pinfunction "P$2_P$2") (pintype "passive"))
      (node (ref "U8") (pin "7") (pinfunction "PB6_7") (pintype "bidirectional"))
      (node (ref "XTAL1") (pin "P$1") (pinfunction "P$1_P$1") (pintype "bidirectional"))
    )
    (net (code "62") (name "XTAL2") (class "Default")
      (node (ref "C13") (pin "P$2") (pinfunction "P$2_P$2") (pintype "passive"))
      (node (ref "U8") (pin "8") (pinfunction "PB7_8") (pintype "bidirectional"))
      (node (ref "XTAL1") (pin "P$2") (pinfunction "P$2_P$2") (pintype "bidirectional"))
    )
    (net (code "63") (name "unconnected-(U8-PB0-Pad12)") (class "Default")
      (node (ref "U8") (pin "12") (pinfunction "PB0_12") (pintype "bidirectional"))
    )
    (net (code "64") (name "unconnected-(U8-PB1-Pad13)") (class "Default")
      (node (ref "U8") (pin "13") (pinfunction "PB1_13") (pintype "bidirectional"))
    )
    (net (code "65") (name "unconnected-(U8-PB2-Pad14)") (class "Default")
      (node (ref "U8") (pin "14") (pinfunction "PB2_14") (pintype "bidirectional"))
    )
    (net (code "66") (name "unconnected-(U8-PC0-Pad23)") (class "Default")
      (node (ref "U8") (pin "23") (pinfunction "PC0_23") (pintype "bidirectional"))
    )
    (net (code "67") (name "unconnected-(U8-PD5-Pad9)") (class "Default")
      (node (ref "U8") (pin "9") (pinfunction "PD5_9") (pintype "bidirectional"))
    )
    (net (code "68") (name "unconnected-(U8-PD6-Pad10)") (class "Default")
      (node (ref "U8") (pin "10") (pinfunction "PD6_10") (pintype "bidirectional"))
    )
    (net (code "69") (name "unconnected-(U8-PD7-Pad11)") (class "Default")
      (node (ref "U8") (pin "11") (pinfunction "PD7_11") (pintype "bidirectional"))
    )
    (net (code "70") (name "unconnected-(U8-PE1-Pad6)") (class "Default")
      (node (ref "U8") (pin "6") (pinfunction "PE1_6") (pintype "bidirectional"))
    )
    (net (code "71") (name "unconnected-(U8-PE2-Pad19)") (class "Default")
      (node (ref "U8") (pin "19") (pinfunction "PE2_19") (pintype "bidirectional"))
    )
    (net (code "72") (name "unconnected-(U8-PE3-Pad22)") (class "Default")
      (node (ref "U8") (pin "22") (pinfunction "PE3_22") (pintype "bidirectional"))
    )
    (net (code "73") (name "~{RESET}") (class "Default")
      (node (ref "JP1") (pin "4") (pinfunction "4_4") (pintype "passive"))
      (node (ref "R28") (pin "P$1") (pinfunction "P$1_P$1") (pintype "passive"))
      (node (ref "U8") (pin "29") (pinfunction "PC6_29") (pintype "bidirectional"))
    )
  )
)
